# NDriveModule.net
KiCad netlist of a schematic drawn in EAGLE
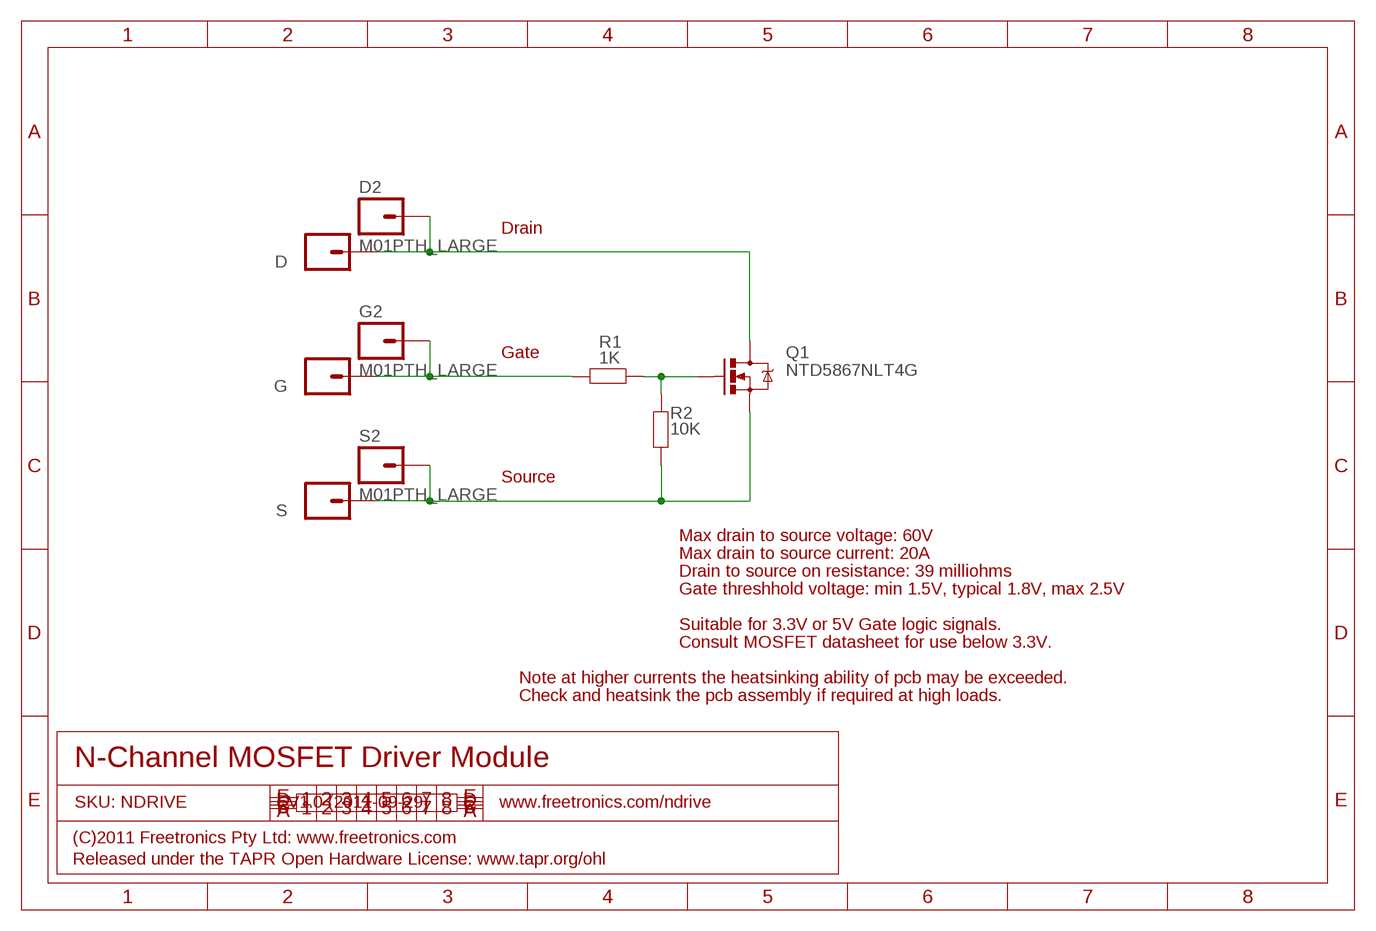
[diagram p0: schematic, sheet 1]

(export (version "E")
  (design (tool "Eeschema 10.0.6"))
  (components
    (comp (ref "D")
      (value "M01PTH")
      (footprint "eagle-import:1X01")
      (libsource (lib "eagle-import") (part "M01PTH"))
    )
    (comp (ref "D2")
      (value "M01PTH_LARGE")
      (footprint "eagle-import:1X01LARGE")
      (libsource (lib "eagle-import") (part "M01PTH_LARGE"))
    )
    (comp (ref "G")
      (value "M01PTH")
      (footprint "eagle-import:1X01")
      (libsource (lib "eagle-import") (part "M01PTH"))
    )
    (comp (ref "G2")
      (value "M01PTH_LARGE")
      (footprint "eagle-import:1X01LARGE")
      (libsource (lib "eagle-import") (part "M01PTH_LARGE"))
    )
    (comp (ref "Q1")
      (value "NTD5867NLT4G")
      (footprint "eagle-import:DPACK")
      (libsource (lib "eagle-import") (part "MOSFET-NCHANNELDPAK"))
    )
    (comp (ref "R1")
      (value "1K")
      (footprint "eagle-import:0603")
      (libsource (lib "eagle-import") (part "RESISTOR0603"))
    )
    (comp (ref "R2")
      (value "10K")
      (footprint "eagle-import:0603")
      (libsource (lib "eagle-import") (part "RESISTOR0603"))
    )
    (comp (ref "S")
      (value "M01PTH")
      (footprint "eagle-import:1X01")
      (libsource (lib "eagle-import") (part "M01PTH"))
    )
    (comp (ref "S2")
      (value "M01PTH_LARGE")
      (footprint "eagle-import:1X01LARGE")
      (libsource (lib "eagle-import") (part "M01PTH_LARGE"))
    )
  )
  (nets
    (net (code "1") (name "Net-(G-Pad1)") (class "Default")
      (node (ref "G") (pin "1") (pinfunction "1_1") (pintype "passive"))
      (node (ref "G2") (pin "1") (pinfunction "1_1") (pintype "passive"))
      (node (ref "R1") (pin "2") (pinfunction "2_2") (pintype "passive"))
    )
    (net (code "2") (name "Net-(Q1-D)") (class "Default")
      (node (ref "D") (pin "1") (pinfunction "1_1") (pintype "passive"))
      (node (ref "D2") (pin "1") (pinfunction "1_1") (pintype "passive"))
      (node (ref "Q1") (pin "2") (pinfunction "D_2") (pintype "passive"))
    )
    (net (code "3") (name "Net-(Q1-G)") (class "Default")
      (node (ref "Q1") (pin "1") (pinfunction "G_1") (pintype "passive"))
      (node (ref "R1") (pin "1") (pinfunction "1_1") (pintype "passive"))
      (node (ref "R2") (pin "2") (pinfunction "2_2") (pintype "passive"))
    )
    (net (code "4") (name "Net-(Q1-S)") (class "Default")
      (node (ref "Q1") (pin "3") (pinfunction "S_3") (pintype "passive"))
      (node (ref "R2") (pin "1") (pinfunction "1_1") (pintype "passive"))
      (node (ref "S") (pin "1") (pinfunction "1_1") (pintype "passive"))
      (node (ref "S2") (pin "1") (pinfunction "1_1") (pintype "passive"))
    )
  )
)
